# Shield_E_Motion.net
KiCad netlist of a schematic drawn in EAGLE
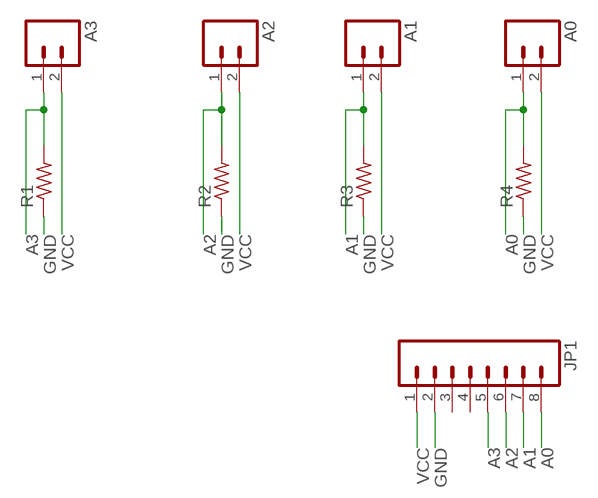
[diagram p0: schematic, sheet 1]

(export (version "E")
  (design (tool "Eeschema 10.0.6"))
  (components
    (comp (ref "A0")
      (value "M02")
      (footprint "eagle-import:1X02_LONGPADS")
      (libsource (lib "eagle-import") (part "M02"))
    )
    (comp (ref "A1")
      (value "M02")
      (footprint "eagle-import:1X02_LONGPADS")
      (libsource (lib "eagle-import") (part "M02"))
    )
    (comp (ref "A2")
      (value "M02")
      (footprint "eagle-import:1X02_LONGPADS")
      (libsource (lib "eagle-import") (part "M02"))
    )
    (comp (ref "A3")
      (value "M02")
      (footprint "eagle-import:1X02_LONGPADS")
      (libsource (lib "eagle-import") (part "M02"))
    )
    (comp (ref "JP1")
      (value "M08LONGPADS")
      (footprint "eagle-import:1X08_LONGPADS")
      (libsource (lib "eagle-import") (part "M08LONGPADS"))
    )
    (comp (ref "R1")
      (value "RESISTOR0402")
      (footprint "eagle-import:0402")
      (libsource (lib "eagle-import") (part "RESISTOR0402"))
    )
    (comp (ref "R2")
      (value "RESISTOR0402")
      (footprint "eagle-import:0402")
      (libsource (lib "eagle-import") (part "RESISTOR0402"))
    )
    (comp (ref "R3")
      (value "RESISTOR0402")
      (footprint "eagle-import:0402")
      (libsource (lib "eagle-import") (part "RESISTOR0402"))
    )
    (comp (ref "R4")
      (value "RESISTOR0402")
      (footprint "eagle-import:0402")
      (libsource (lib "eagle-import") (part "RESISTOR0402"))
    )
  )
  (nets
    (net (code "1") (name "/A0") (class "Default")
      (node (ref "A0") (pin "1") (pinfunction "1_1") (pintype "passive"))
      (node (ref "JP1") (pin "8") (pinfunction "8_8") (pintype "passive"))
      (node (ref "R4") (pin "2") (pinfunction "2_2") (pintype "passive"))
    )
    (net (code "2") (name "/A1") (class "Default")
      (node (ref "A1") (pin "1") (pinfunction "1_1") (pintype "passive"))
      (node (ref "JP1") (pin "7") (pinfunction "7_7") (pintype "passive"))
      (node (ref "R3") (pin "2") (pinfunction "2_2") (pintype "passive"))
    )
    (net (code "3") (name "/A2") (class "Default")
      (node (ref "A2") (pin "1") (pinfunction "1_1") (pintype "passive"))
      (node (ref "JP1") (pin "6") (pinfunction "6_6") (pintype "passive"))
      (node (ref "R2") (pin "2") (pinfunction "2_2") (pintype "passive"))
    )
    (net (code "4") (name "/A3") (class "Default")
      (node (ref "A3") (pin "1") (pinfunction "1_1") (pintype "passive"))
      (node (ref "JP1") (pin "5") (pinfunction "5_5") (pintype "passive"))
      (node (ref "R1") (pin "2") (pinfunction "2_2") (pintype "passive"))
    )
    (net (code "5") (name "/GND") (class "Default")
      (node (ref "JP1") (pin "2") (pinfunction "2_2") (pintype "passive"))
      (node (ref "R1") (pin "1") (pinfunction "1_1") (pintype "passive"))
      (node (ref "R2") (pin "1") (pinfunction "1_1") (pintype "passive"))
      (node (ref "R3") (pin "1") (pinfunction "1_1") (pintype "passive"))
      (node (ref "R4") (pin "1") (pinfunction "1_1") (pintype "passive"))
    )
    (net (code "6") (name "/VCC") (class "Default")
      (node (ref "A0") (pin "2") (pinfunction "2_2") (pintype "passive"))
      (node (ref "A1") (pin "2") (pinfunction "2_2") (pintype "passive"))
      (node (ref "A2") (pin "2") (pinfunction "2_2") (pintype "passive"))
      (node (ref "A3") (pin "2") (pinfunction "2_2") (pintype "passive"))
      (node (ref "JP1") (pin "1") (pinfunction "1_1") (pintype "passive"))
    )
    (net (code "7") (name "unconnected-(JP1-Pad3)") (class "Default")
      (node (ref "JP1") (pin "3") (pinfunction "3_3") (pintype "passive"))
    )
    (net (code "8") (name "unconnected-(JP1-Pad4)") (class "Default")
      (node (ref "JP1") (pin "4") (pinfunction "4_4") (pintype "passive"))
    )
  )
)
